# DOC-00001.net
KiCad netlist of a schematic drawn in EAGLE
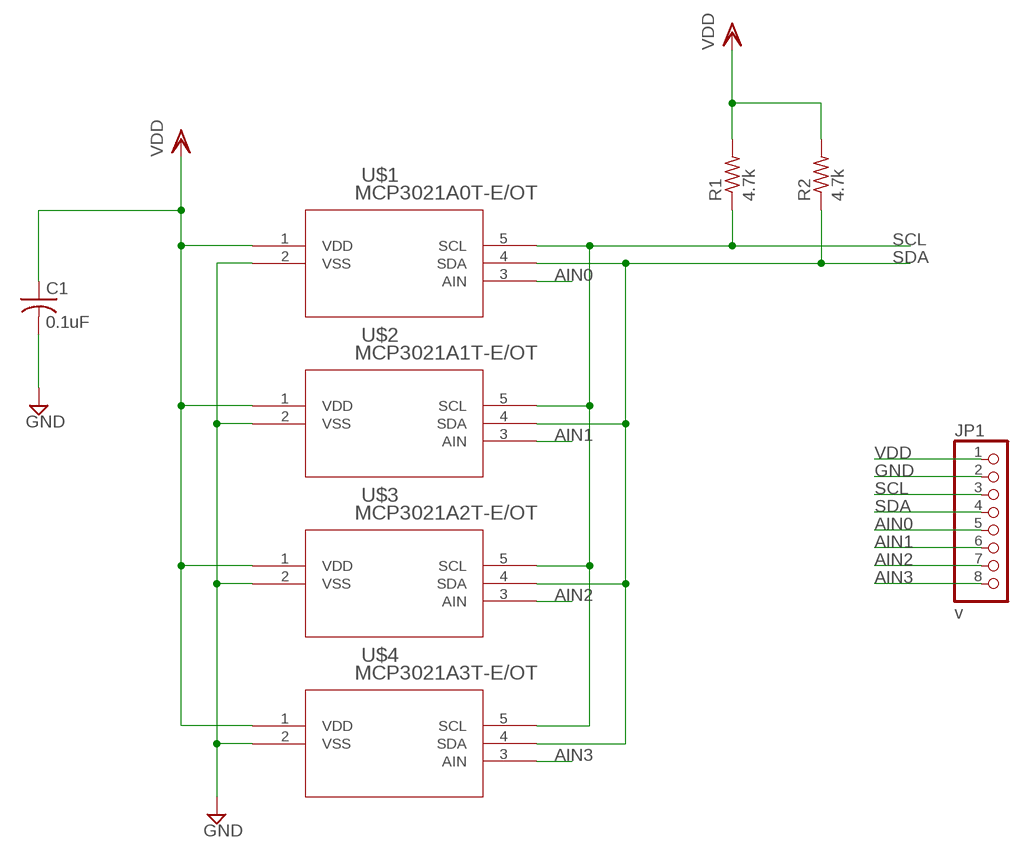
[diagram p0: schematic, sheet 1]

(export (version "E")
  (design (tool "Eeschema 10.0.6"))
  (components
    (comp (ref "C1")
      (value "0.1uF")
      (footprint "eagle-import:C0805K")
      (fields (field (name "MPN") "VJ0805Y104MXXAC"))
      (libsource (lib "eagle-import") (part "C-USC0805K"))
    )
    (comp (ref "JP1")
      (value "v")
      (footprint "eagle-import:1X08")
      (fields (field (name "MPN") "825433-8"))
      (libsource (lib "eagle-import") (part "PINHD-1X8"))
    )
    (comp (ref "R1")
      (value "4.7k")
      (footprint "eagle-import:R0805")
      (fields (field (name "MPN") "CRCW08054K70FKEA"))
      (libsource (lib "eagle-import") (part "R-US_R0805"))
    )
    (comp (ref "R2")
      (value "4.7k")
      (footprint "eagle-import:R0805")
      (fields (field (name "MPN") "CRCW08054K70FKEA"))
      (libsource (lib "eagle-import") (part "R-US_R0805"))
    )
    (comp (ref "U$1")
      (value "MCP3021A0T-E/OT")
      (footprint "eagle-import:SOT-23-5_MC")
      (libsource (lib "eagle-import") (part "MCP3021XX-X/OT"))
    )
    (comp (ref "U$2")
      (value "MCP3021A1T-E/OT")
      (footprint "eagle-import:SOT-23-5_MC")
      (libsource (lib "eagle-import") (part "MCP3021XX-X/OT"))
    )
    (comp (ref "U$3")
      (value "MCP3021A2T-E/OT")
      (footprint "eagle-import:SOT-23-5_MC")
      (libsource (lib "eagle-import") (part "MCP3021XX-X/OT"))
    )
    (comp (ref "U$4")
      (value "MCP3021A3T-E/OT")
      (footprint "eagle-import:SOT-23-5_MC")
      (libsource (lib "eagle-import") (part "MCP3021XX-X/OT"))
    )
  )
  (nets
    (net (code "1") (name "/AIN0") (class "Default")
      (node (ref "JP1") (pin "5") (pinfunction "5_5") (pintype "passive"))
      (node (ref "U$1") (pin "3") (pinfunction "AIN_3") (pintype "passive"))
    )
    (net (code "2") (name "/AIN1") (class "Default")
      (node (ref "JP1") (pin "6") (pinfunction "6_6") (pintype "passive"))
      (node (ref "U$2") (pin "3") (pinfunction "AIN_3") (pintype "passive"))
    )
    (net (code "3") (name "/AIN2") (class "Default")
      (node (ref "JP1") (pin "7") (pinfunction "7_7") (pintype "passive"))
      (node (ref "U$3") (pin "3") (pinfunction "AIN_3") (pintype "passive"))
    )
    (net (code "4") (name "/AIN3") (class "Default")
      (node (ref "JP1") (pin "8") (pinfunction "8_8") (pintype "passive"))
      (node (ref "U$4") (pin "3") (pinfunction "AIN_3") (pintype "passive"))
    )
    (net (code "5") (name "/SCL") (class "Default")
      (node (ref "JP1") (pin "3") (pinfunction "3_3") (pintype "passive"))
      (node (ref "R1") (pin "1") (pinfunction "1_1") (pintype "passive"))
      (node (ref "U$1") (pin "5") (pinfunction "SCL_5") (pintype "passive"))
      (node (ref "U$2") (pin "5") (pinfunction "SCL_5") (pintype "passive"))
      (node (ref "U$3") (pin "5") (pinfunction "SCL_5") (pintype "passive"))
      (node (ref "U$4") (pin "5") (pinfunction "SCL_5") (pintype "passive"))
    )
    (net (code "6") (name "/SDA") (class "Default")
      (node (ref "JP1") (pin "4") (pinfunction "4_4") (pintype "passive"))
      (node (ref "R2") (pin "1") (pinfunction "1_1") (pintype "passive"))
      (node (ref "U$1") (pin "4") (pinfunction "SDA_4") (pintype "passive"))
      (node (ref "U$2") (pin "4") (pinfunction "SDA_4") (pintype "passive"))
      (node (ref "U$3") (pin "4") (pinfunction "SDA_4") (pintype "passive"))
      (node (ref "U$4") (pin "4") (pinfunction "SDA_4") (pintype "passive"))
    )
    (net (code "7") (name "GND") (class "Default")
      (node (ref "C1") (pin "2") (pinfunction "2_2") (pintype "passive"))
      (node (ref "JP1") (pin "2") (pinfunction "2_2") (pintype "passive"))
      (node (ref "U$1") (pin "2") (pinfunction "VSS_2") (pintype "passive"))
      (node (ref "U$2") (pin "2") (pinfunction "VSS_2") (pintype "passive"))
      (node (ref "U$3") (pin "2") (pinfunction "VSS_2") (pintype "passive"))
      (node (ref "U$4") (pin "2") (pinfunction "VSS_2") (pintype "passive"))
    )
    (net (code "8") (name "VDD") (class "Default")
      (node (ref "C1") (pin "1") (pinfunction "1_1") (pintype "passive"))
      (node (ref "JP1") (pin "1") (pinfunction "1_1") (pintype "passive"))
      (node (ref "R1") (pin "2") (pinfunction "2_2") (pintype "passive"))
      (node (ref "R2") (pin "2") (pinfunction "2_2") (pintype "passive"))
      (node (ref "U$1") (pin "1") (pinfunction "VDD_1") (pintype "passive"))
      (node (ref "U$2") (pin "1") (pinfunction "VDD_1") (pintype "passive"))
      (node (ref "U$3") (pin "1") (pinfunction "VDD_1") (pintype "passive"))
      (node (ref "U$4") (pin "1") (pinfunction "VDD_1") (pintype "passive"))
    )
  )
)
